# transmittor_distance.net
KiCad netlist of a schematic drawn in EAGLE
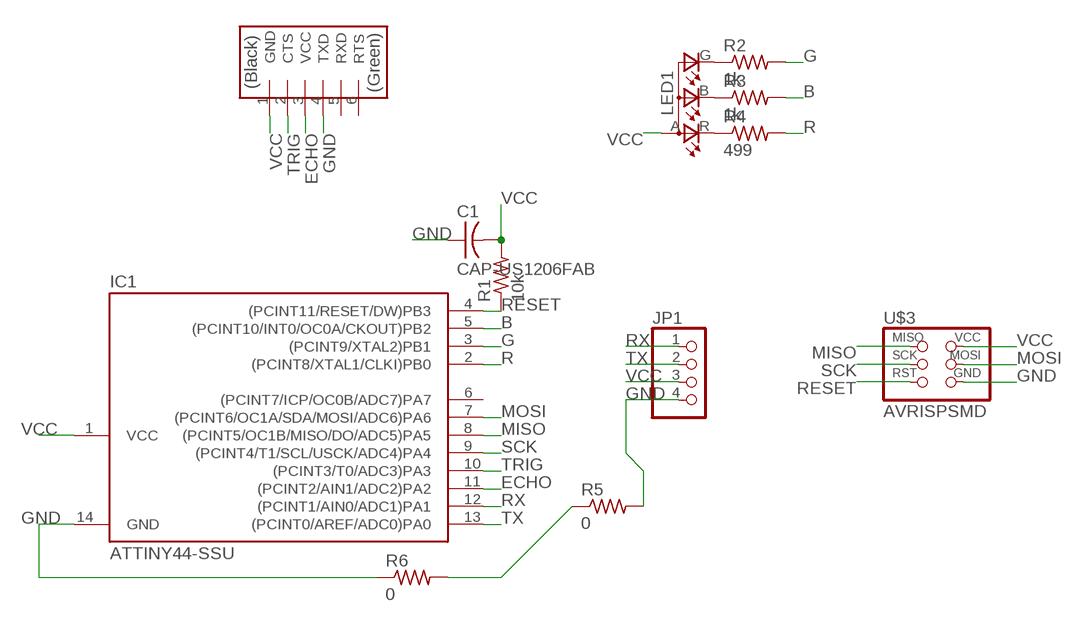
[diagram p0: schematic, sheet 1]

(export (version "E")
  (design (tool "Eeschema 10.0.6"))
  (components
    (comp (ref "C1")
      (value "CAP-US1206FAB")
      (footprint "eagle-import:C1206FAB")
      (libsource (lib "eagle-import") (part "CAP-US1206FAB"))
    )
    (comp (ref "IC1")
      (value "ATTINY44-SSU")
      (footprint "eagle-import:SOIC14")
      (libsource (lib "eagle-import") (part "ATTINY44-SSU"))
    )
    (comp (ref "JP1")
      (value "PINHD-1X4")
      (footprint "eagle-import:1X04")
      (libsource (lib "eagle-import") (part "PINHD-1X4"))
    )
    (comp (ref "LED1")
      (value "LEDRGBOLD")
      (footprint "eagle-import:P-LCC-4-3")
      (libsource (lib "eagle-import") (part "LEDRGBOLD"))
    )
    (comp (ref "R1")
      (value "10k")
      (footprint "eagle-import:R1206FAB")
      (libsource (lib "eagle-import") (part "RES-US1206FAB"))
    )
    (comp (ref "R2")
      (value "1k")
      (footprint "eagle-import:R1206FAB")
      (libsource (lib "eagle-import") (part "RES-US1206FAB"))
    )
    (comp (ref "R3")
      (value "1k")
      (footprint "eagle-import:R1206FAB")
      (libsource (lib "eagle-import") (part "RES-US1206FAB"))
    )
    (comp (ref "R4")
      (value "499")
      (footprint "eagle-import:R1206FAB")
      (libsource (lib "eagle-import") (part "RES-US1206FAB"))
    )
    (comp (ref "R5")
      (value "0")
      (footprint "eagle-import:R1206FAB")
      (libsource (lib "eagle-import") (part "RES-US1206FAB"))
    )
    (comp (ref "R6")
      (value "0")
      (footprint "eagle-import:R1206FAB")
      (libsource (lib "eagle-import") (part "RES-US1206FAB"))
    )
    (comp (ref "U$1")
      (value "FTDI-SMD-HEADER")
      (footprint "eagle-import:1X06SMD")
      (libsource (lib "eagle-import") (part "FTDI-SMD-HEADER"))
    )
    (comp (ref "U$3")
      (value "AVRISPSMD")
      (footprint "eagle-import:2X03SMD")
      (libsource (lib "eagle-import") (part "AVRISPSMD"))
    )
  )
  (nets
    (net (code "1") (name "/B") (class "Default")
      (node (ref "IC1") (pin "5") (pinfunction "(PCINT10/INT0/OC0A/CKOUT)PB2_5") (pintype "bidirectional"))
      (node (ref "R3") (pin "2") (pinfunction "2_2") (pintype "passive"))
    )
    (net (code "2") (name "/ECHO") (class "Default")
      (node (ref "IC1") (pin "11") (pinfunction "(PCINT2/AIN1/ADC2)PA2_11") (pintype "bidirectional"))
      (node (ref "U$1") (pin "3") (pinfunction "VCC_3") (pintype "bidirectional"))
    )
    (net (code "3") (name "/G") (class "Default")
      (node (ref "IC1") (pin "3") (pinfunction "(PCINT9/XTAL2)PB1_3") (pintype "bidirectional"))
      (node (ref "R2") (pin "2") (pinfunction "2_2") (pintype "passive"))
    )
    (net (code "4") (name "/GND") (class "Default")
      (node (ref "C1") (pin "1") (pinfunction "1_1") (pintype "passive"))
      (node (ref "IC1") (pin "14") (pinfunction "GND_14") (pintype "power_in"))
      (node (ref "JP1") (pin "4") (pinfunction "4_4") (pintype "passive"))
      (node (ref "R5") (pin "2") (pinfunction "2_2") (pintype "passive"))
      (node (ref "R6") (pin "1") (pinfunction "1_1") (pintype "passive"))
      (node (ref "U$1") (pin "4") (pinfunction "TXD_4") (pintype "bidirectional"))
      (node (ref "U$3") (pin "6") (pinfunction "GND_6") (pintype "passive"))
    )
    (net (code "5") (name "/MISO") (class "Default")
      (node (ref "IC1") (pin "8") (pinfunction "(PCINT5/OC1B/MISO/DO/ADC5)PA5_8") (pintype "bidirectional"))
      (node (ref "U$3") (pin "1") (pinfunction "MISO_1") (pintype "passive"))
    )
    (net (code "6") (name "/MOSI") (class "Default")
      (node (ref "IC1") (pin "7") (pinfunction "(PCINT6/OC1A/SDA/MOSI/ADC6)PA6_7") (pintype "bidirectional"))
      (node (ref "U$3") (pin "4") (pinfunction "MOSI_4") (pintype "passive"))
    )
    (net (code "7") (name "/R") (class "Default")
      (node (ref "IC1") (pin "2") (pinfunction "(PCINT8/XTAL1/CLKI)PB0_2") (pintype "bidirectional"))
      (node (ref "R4") (pin "2") (pinfunction "2_2") (pintype "passive"))
    )
    (net (code "8") (name "/RESET") (class "Default")
      (node (ref "IC1") (pin "4") (pinfunction "(PCINT11/RESET/DW)PB3_4") (pintype "bidirectional"))
      (node (ref "R1") (pin "1") (pinfunction "1_1") (pintype "passive"))
      (node (ref "U$3") (pin "5") (pinfunction "RST_5") (pintype "passive"))
    )
    (net (code "9") (name "/RX") (class "Default")
      (node (ref "IC1") (pin "12") (pinfunction "(PCINT1/AIN0/ADC1)PA1_12") (pintype "bidirectional"))
      (node (ref "JP1") (pin "1") (pinfunction "1_1") (pintype "passive"))
    )
    (net (code "10") (name "/SCK") (class "Default")
      (node (ref "IC1") (pin "9") (pinfunction "(PCINT4/T1/SCL/USCK/ADC4)PA4_9") (pintype "bidirectional"))
      (node (ref "U$3") (pin "3") (pinfunction "SCK_3") (pintype "passive"))
    )
    (net (code "11") (name "/TRIG") (class "Default")
      (node (ref "IC1") (pin "10") (pinfunction "(PCINT3/T0/ADC3)PA3_10") (pintype "bidirectional"))
      (node (ref "U$1") (pin "2") (pinfunction "CTS_2") (pintype "bidirectional"))
    )
    (net (code "12") (name "/TX") (class "Default")
      (node (ref "IC1") (pin "13") (pinfunction "(PCINT0/AREF/ADC0)PA0_13") (pintype "bidirectional"))
      (node (ref "JP1") (pin "2") (pinfunction "2_2") (pintype "passive"))
    )
    (net (code "13") (name "/VCC") (class "Default")
      (node (ref "C1") (pin "2") (pinfunction "2_2") (pintype "passive"))
      (node (ref "IC1") (pin "1") (pinfunction "VCC_1") (pintype "power_in"))
      (node (ref "JP1") (pin "3") (pinfunction "3_3") (pintype "passive"))
      (node (ref "LED1") (pin "A") (pinfunction "A2_A") (pintype "passive"))
      (node (ref "R1") (pin "2") (pinfunction "2_2") (pintype "passive"))
      (node (ref "U$1") (pin "1") (pinfunction "GND_1") (pintype "bidirectional"))
      (node (ref "U$3") (pin "2") (pinfunction "VCC_2") (pintype "passive"))
    )
    (net (code "14") (name "Net-(LED1-CBLUE)") (class "Default")
      (node (ref "LED1") (pin "B") (pinfunction "CBLUE_B") (pintype "passive"))
      (node (ref "R3") (pin "1") (pinfunction "1_1") (pintype "passive"))
    )
    (net (code "15") (name "Net-(LED1-CGREEN)") (class "Default")
      (node (ref "LED1") (pin "G") (pinfunction "CGREEN_G") (pintype "passive"))
      (node (ref "R2") (pin "1") (pinfunction "1_1") (pintype "passive"))
    )
    (net (code "16") (name "Net-(LED1-CRED)") (class "Default")
      (node (ref "LED1") (pin "R") (pinfunction "CRED_R") (pintype "passive"))
      (node (ref "R4") (pin "1") (pinfunction "1_1") (pintype "passive"))
    )
    (net (code "17") (name "Net-(R5-Pad1)") (class "Default")
      (node (ref "R5") (pin "1") (pinfunction "1_1") (pintype "passive"))
      (node (ref "R6") (pin "2") (pinfunction "2_2") (pintype "passive"))
    )
    (net (code "18") (name "unconnected-(IC1-(PCINT7{slash}ICP{slash}OC0B{slash}ADC7)PA7-Pad6)") (class "Default")
      (node (ref "IC1") (pin "6") (pinfunction "(PCINT7/ICP/OC0B/ADC7)PA7_6") (pintype "bidirectional"))
    )
    (net (code "19") (name "unconnected-(U$1-RTS-Pad6)") (class "Default")
      (node (ref "U$1") (pin "6") (pinfunction "RTS_6") (pintype "bidirectional"))
    )
    (net (code "20") (name "unconnected-(U$1-RXD-Pad5)") (class "Default")
      (node (ref "U$1") (pin "5") (pinfunction "RXD_5") (pintype "bidirectional"))
    )
  )
)
